# RPS_ARMOR_PCB_2022_V1_0.net
KiCad netlist of a schematic drawn in Altium Designer
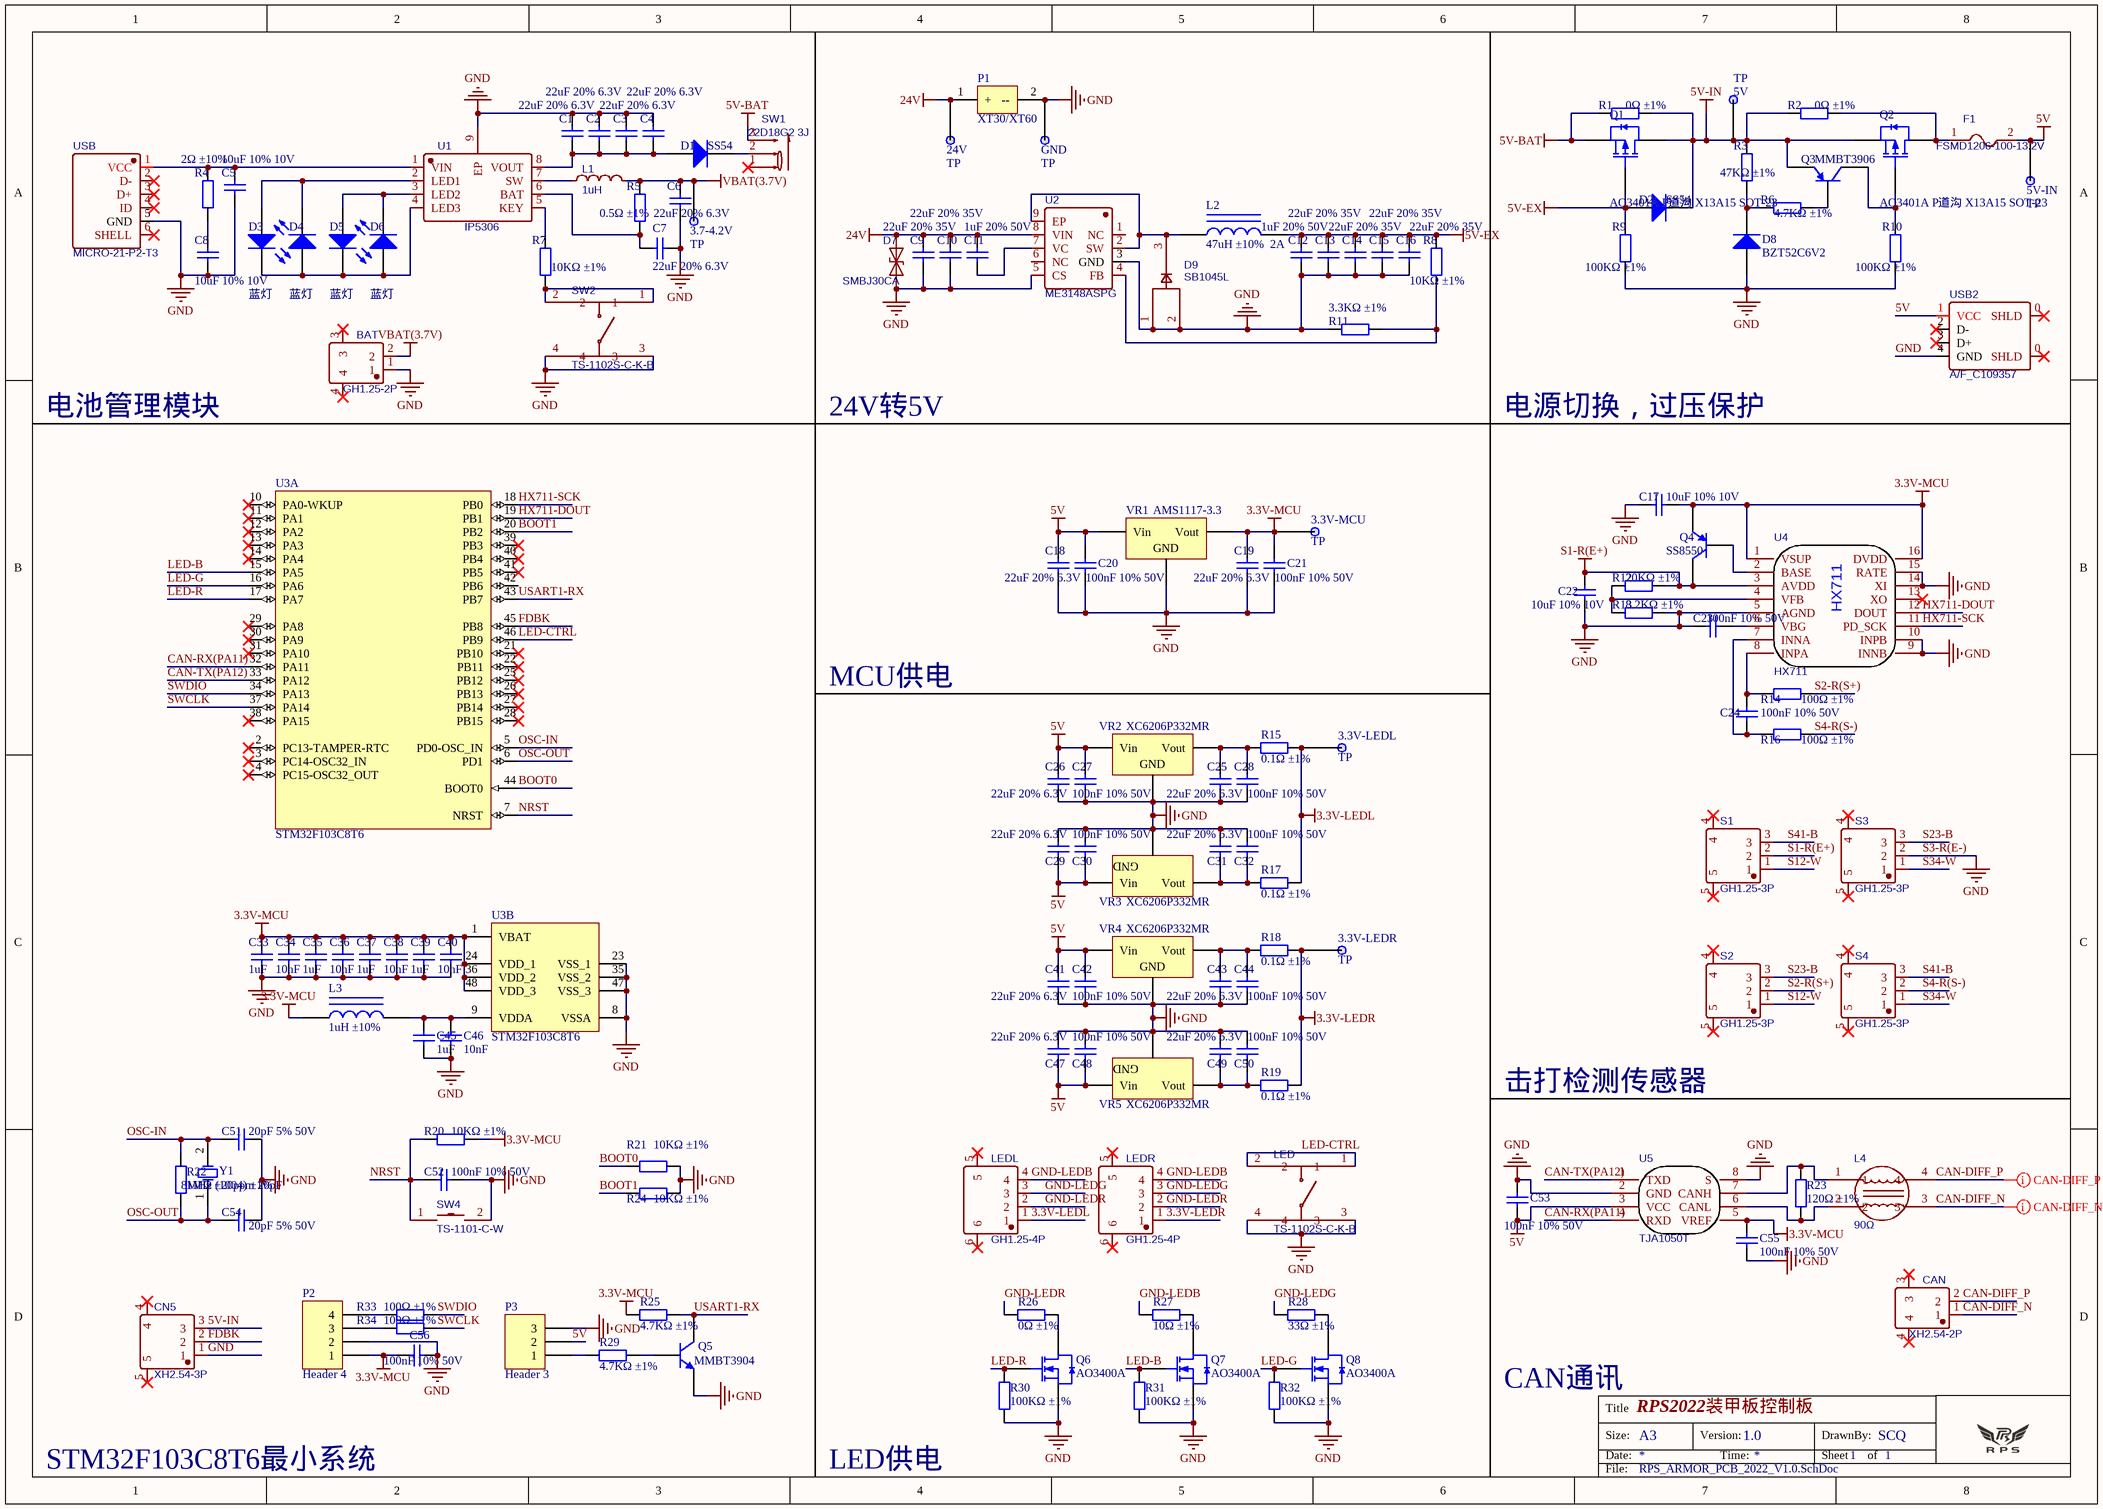
[diagram p0: RPS_ARMOR_PCB_2022_V1.0.SchDoc]

(export (version "E")
  (design (tool "Eeschema 10.0.6"))
  (components
    (comp (ref "3.3V-LEDL")
      (value "TP")
      (footprint "TP")
      (description "测试点")
      (libsource (lib "RPS_ARMOR_PCB_2022_V1.0") (part "TP"))
    )
    (comp (ref "3.3V-LEDR")
      (value "TP")
      (footprint "TP")
      (description "测试点")
      (libsource (lib "RPS_ARMOR_PCB_2022_V1.0") (part "TP"))
    )
    (comp (ref "3.3V-MCU")
      (value "TP")
      (footprint "TP")
      (description "测试点")
      (libsource (lib "RPS_ARMOR_PCB_2022_V1.0") (part "TP"))
    )
    (comp (ref "3.7-4.2V")
      (value "TP")
      (footprint "TP")
      (description "测试点")
      (libsource (lib "RPS_ARMOR_PCB_2022_V1.0") (part "TP"))
    )
    (comp (ref "5V")
      (value "TP")
      (footprint "TP")
      (description "测试点")
      (libsource (lib "RPS_ARMOR_PCB_2022_V1.0") (part "TP"))
    )
    (comp (ref "5V-IN")
      (value "TP")
      (footprint "TP")
      (description "测试点")
      (libsource (lib "RPS_ARMOR_PCB_2022_V1.0") (part "TP"))
    )
    (comp (ref "24V")
      (value "TP")
      (footprint "TP")
      (description "测试点")
      (libsource (lib "RPS_ARMOR_PCB_2022_V1.0") (part "TP"))
    )
    (comp (ref "BAT")
      (value "GH1.25-2P")
      (footprint "GH1.25-WS-2P")
      (description "GH1.25端子")
      (fields
        (field (name "BOM_SUPPLIER PART") "C225125")
        (field (name "BOM_MANUFACTURER PART") "A1257WR-S-2P")
        (field (name "CONTRIBUTOR") "LCSC")
      )
      (libsource (lib "RPS_ARMOR_PCB_2022_V1.0") (part "GH1.25-2P"))
    )
    (comp (ref "C1")
      (value "22uF 20% 6.3V")
      (footprint "0603_C")
      (description "C109448")
      (libsource (lib "Miscellaneous Devices LC") (part "0603 22uF (226) 20% 6.3V"))
    )
    (comp (ref "C2")
      (value "22uF 20% 6.3V")
      (footprint "0603_C")
      (description "C109448")
      (libsource (lib "Miscellaneous Devices LC") (part "0603 22uF (226) 20% 6.3V"))
    )
    (comp (ref "C3")
      (value "22uF 20% 6.3V")
      (footprint "0603_C")
      (description "C109448")
      (libsource (lib "Miscellaneous Devices LC") (part "0603 22uF (226) 20% 6.3V"))
    )
    (comp (ref "C4")
      (value "22uF 20% 6.3V")
      (footprint "0603_C")
      (description "C109448")
      (libsource (lib "Miscellaneous Devices LC") (part "0603 22uF (226) 20% 6.3V"))
    )
    (comp (ref "C5")
      (value "10uF 10% 10V")
      (footprint "0603_C")
      (description "C19702")
      (libsource (lib "Miscellaneous Devices LC") (part "0603 10uF (106) 10% 10V"))
    )
    (comp (ref "C6")
      (value "22uF 20% 6.3V")
      (footprint "0603_C")
      (description "C109448")
      (libsource (lib "Miscellaneous Devices LC") (part "0603 22uF (226) 20% 6.3V"))
    )
    (comp (ref "C7")
      (value "22uF 20% 6.3V")
      (footprint "0603_C")
      (description "C109448")
      (libsource (lib "Miscellaneous Devices LC") (part "0603 22uF (226) 20% 6.3V"))
    )
    (comp (ref "C8")
      (value "10uF 10% 10V")
      (footprint "0603_C")
      (description "C19702")
      (libsource (lib "Miscellaneous Devices LC") (part "0603 10uF (106) 10% 10V"))
    )
    (comp (ref "C9")
      (value "22uF 20% 35V")
      (footprint "1206_C")
      (description "C2835503")
      (libsource (lib "Miscellaneous Devices LC") (part "1206 10uF (106) 10% 50V"))
    )
    (comp (ref "C10")
      (value "22uF 20% 35V")
      (footprint "1206_C")
      (description "C2835503")
      (libsource (lib "Miscellaneous Devices LC") (part "1206 10uF (106) 10% 50V"))
    )
    (comp (ref "C11")
      (value "1uF 20% 50V")
      (footprint "0805_C")
      (description "C2217678")
      (libsource (lib "Miscellaneous Devices LC") (part "0805 1uF (105) 10% 50V"))
    )
    (comp (ref "C12")
      (value "1uF 20% 50V")
      (footprint "0805_C")
      (description "C2217678")
      (libsource (lib "Miscellaneous Devices LC") (part "0805 1uF (105) 10% 50V"))
    )
    (comp (ref "C13")
      (value "22uF 20% 35V")
      (footprint "1206_C")
      (description "C2835503")
      (libsource (lib "Miscellaneous Devices LC") (part "1206 10uF (106) 10% 50V"))
    )
    (comp (ref "C14")
      (value "22uF 20% 35V")
      (footprint "1206_C")
      (description "C2835503")
      (libsource (lib "Miscellaneous Devices LC") (part "1206 10uF (106) 10% 50V"))
    )
    (comp (ref "C15")
      (value "22uF 20% 35V")
      (footprint "1206_C")
      (description "C2835503")
      (libsource (lib "Miscellaneous Devices LC") (part "1206 10uF (106) 10% 50V"))
    )
    (comp (ref "C16")
      (value "22uF 20% 35V")
      (footprint "1206_C")
      (description "C2835503")
      (libsource (lib "Miscellaneous Devices LC") (part "1206 10uF (106) 10% 50V"))
    )
    (comp (ref "C17")
      (value "10uF 10% 10V")
      (footprint "0603_C")
      (description "贴片电容")
      (libsource (lib "Miscellaneous Devices LC") (part "0603 10uF (106) 10% 10V"))
    )
    (comp (ref "C18")
      (value "22uF 20% 6.3V")
      (footprint "0603_C")
      (description "C109448")
      (libsource (lib "Miscellaneous Devices LC") (part "0603 22uF (226) 20% 6.3V"))
    )
    (comp (ref "C19")
      (value "22uF 20% 6.3V")
      (footprint "0603_C")
      (description "C109448")
      (libsource (lib "Miscellaneous Devices LC") (part "0603 22uF (226) 20% 6.3V"))
    )
    (comp (ref "C20")
      (value "100nF 10% 50V")
      (footprint "0603_C")
      (description "贴片电容")
      (libsource (lib "Miscellaneous Devices LC") (part "0603 100nF (104) 10% 50V"))
    )
    (comp (ref "C21")
      (value "100nF 10% 50V")
      (footprint "0603_C")
      (description "贴片电容")
      (libsource (lib "Miscellaneous Devices LC") (part "0603 100nF (104) 10% 50V"))
    )
    (comp (ref "C22")
      (value "10uF 10% 10V")
      (footprint "0603_C")
      (description "贴片电容")
      (libsource (lib "Miscellaneous Devices LC") (part "0603 10uF (106) 10% 10V"))
    )
    (comp (ref "C23")
      (value "100nF 10% 50V")
      (footprint "0603_C")
      (description "贴片电容")
      (libsource (lib "Miscellaneous Devices LC") (part "0603 100nF (104) 10% 50V"))
    )
    (comp (ref "C24")
      (value "100nF 10% 50V")
      (footprint "0603_C")
      (description "贴片电容")
      (libsource (lib "Miscellaneous Devices LC") (part "0603 100nF (104) 10% 50V"))
    )
    (comp (ref "C25")
      (value "22uF 20% 6.3V")
      (footprint "0603_C")
      (description "C109448")
      (libsource (lib "Miscellaneous Devices LC") (part "0603 22uF (226) 20% 6.3V"))
    )
    (comp (ref "C26")
      (value "22uF 20% 6.3V")
      (footprint "0603_C")
      (description "C109448")
      (libsource (lib "Miscellaneous Devices LC") (part "0603 22uF (226) 20% 6.3V"))
    )
    (comp (ref "C27")
      (value "100nF 10% 50V")
      (footprint "0603_C")
      (description "贴片电容")
      (libsource (lib "Miscellaneous Devices LC") (part "0603 100nF (104) 10% 50V"))
    )
    (comp (ref "C28")
      (value "100nF 10% 50V")
      (footprint "0603_C")
      (description "贴片电容")
      (libsource (lib "Miscellaneous Devices LC") (part "0603 100nF (104) 10% 50V"))
    )
    (comp (ref "C29")
      (value "22uF 20% 6.3V")
      (footprint "0603_C")
      (description "C109448")
      (libsource (lib "Miscellaneous Devices LC") (part "0603 22uF (226) 20% 6.3V"))
    )
    (comp (ref "C30")
      (value "100nF 10% 50V")
      (footprint "0603_C")
      (description "贴片电容")
      (libsource (lib "Miscellaneous Devices LC") (part "0603 100nF (104) 10% 50V"))
    )
    (comp (ref "C31")
      (value "22uF 20% 6.3V")
      (footprint "0603_C")
      (description "C109448")
      (libsource (lib "Miscellaneous Devices LC") (part "0603 22uF (226) 20% 6.3V"))
    )
    (comp (ref "C32")
      (value "100nF 10% 50V")
      (footprint "0603_C")
      (description "贴片电容")
      (libsource (lib "Miscellaneous Devices LC") (part "0603 100nF (104) 10% 50V"))
    )
    (comp (ref "C33")
      (value "1uF")
      (footprint "0603_C")
      (description "贴片电容")
      (libsource (lib "Miscellaneous Devices LC") (part "0603 1uF (105) 10% 50V"))
    )
    (comp (ref "C34")
      (value "10nF")
      (footprint "0603_C")
      (description "贴片电容")
      (libsource (lib "Miscellaneous Devices LC") (part "0603 10nF (103) 10% 50V"))
    )
    (comp (ref "C35")
      (value "1uF")
      (footprint "0603_C")
      (description "贴片电容")
      (libsource (lib "Miscellaneous Devices LC") (part "0603 1uF (105) 10% 50V"))
    )
    (comp (ref "C36")
      (value "10nF")
      (footprint "0603_C")
      (description "贴片电容")
      (libsource (lib "Miscellaneous Devices LC") (part "0603 10nF (103) 10% 50V"))
    )
    (comp (ref "C37")
      (value "1uF")
      (footprint "0603_C")
      (description "贴片电容")
      (libsource (lib "Miscellaneous Devices LC") (part "0603 1uF (105) 10% 50V"))
    )
    (comp (ref "C38")
      (value "10nF")
      (footprint "0603_C")
      (description "贴片电容")
      (libsource (lib "Miscellaneous Devices LC") (part "0603 10nF (103) 10% 50V"))
    )
    (comp (ref "C39")
      (value "1uF")
      (footprint "0603_C")
      (description "贴片电容")
      (libsource (lib "Miscellaneous Devices LC") (part "0603 1uF (105) 10% 50V"))
    )
    (comp (ref "C40")
      (value "10nF")
      (footprint "0603_C")
      (description "贴片电容")
      (libsource (lib "Miscellaneous Devices LC") (part "0603 10nF (103) 10% 50V"))
    )
    (comp (ref "C41")
      (value "22uF 20% 6.3V")
      (footprint "0603_C")
      (description "C109448")
      (libsource (lib "Miscellaneous Devices LC") (part "0603 22uF (226) 20% 6.3V"))
    )
    (comp (ref "C42")
      (value "100nF 10% 50V")
      (footprint "0603_C")
      (description "贴片电容")
      (libsource (lib "Miscellaneous Devices LC") (part "0603 100nF (104) 10% 50V"))
    )
    (comp (ref "C43")
      (value "22uF 20% 6.3V")
      (footprint "0603_C")
      (description "C109448")
      (libsource (lib "Miscellaneous Devices LC") (part "0603 22uF (226) 20% 6.3V"))
    )
    (comp (ref "C44")
      (value "100nF 10% 50V")
      (footprint "0603_C")
      (description "贴片电容")
      (libsource (lib "Miscellaneous Devices LC") (part "0603 100nF (104) 10% 50V"))
    )
    (comp (ref "C45")
      (value "1uF")
      (footprint "0603_C")
      (description "贴片电容")
      (libsource (lib "Miscellaneous Devices LC") (part "0603 1uF (105) 10% 50V"))
    )
    (comp (ref "C46")
      (value "10nF")
      (footprint "0603_C")
      (description "贴片电容")
      (libsource (lib "Miscellaneous Devices LC") (part "0603 10nF (103) 10% 50V"))
    )
    (comp (ref "C47")
      (value "22uF 20% 6.3V")
      (footprint "0603_C")
      (description "C109448")
      (libsource (lib "Miscellaneous Devices LC") (part "0603 22uF (226) 20% 6.3V"))
    )
    (comp (ref "C48")
      (value "100nF 10% 50V")
      (footprint "0603_C")
      (description "贴片电容")
      (libsource (lib "Miscellaneous Devices LC") (part "0603 100nF (104) 10% 50V"))
    )
    (comp (ref "C49")
      (value "22uF 20% 6.3V")
      (footprint "0603_C")
      (description "C109448")
      (libsource (lib "Miscellaneous Devices LC") (part "0603 22uF (226) 20% 6.3V"))
    )
    (comp (ref "C50")
      (value "100nF 10% 50V")
      (footprint "0603_C")
      (description "贴片电容")
      (libsource (lib "Miscellaneous Devices LC") (part "0603 100nF (104) 10% 50V"))
    )
    (comp (ref "C51")
      (value "20pF 5% 50V")
      (footprint "0603_C")
      (description "贴片电容")
      (libsource (lib "Miscellaneous Devices LC") (part "0603 20pF (200) 5% 50V"))
    )
    (comp (ref "C52")
      (value "100nF 10% 50V")
      (footprint "0603_C")
      (description "贴片电容")
      (libsource (lib "Miscellaneous Devices LC") (part "0603 100nF (104) 10% 50V"))
    )
    (comp (ref "C53")
      (value "100nF 10% 50V")
      (footprint "0603_C")
      (description "贴片电容")
      (libsource (lib "Miscellaneous Devices LC") (part "0603 100nF (104) 10% 50V"))
    )
    (comp (ref "C54")
      (value "20pF 5% 50V")
      (footprint "0603_C")
      (description "贴片电容")
      (libsource (lib "Miscellaneous Devices LC") (part "0603 20pF (200) 5% 50V"))
    )
    (comp (ref "C55")
      (value "100nF 10% 50V")
      (footprint "0603_C")
      (description "贴片电容")
      (libsource (lib "Miscellaneous Devices LC") (part "0603 100nF (104) 10% 50V"))
    )
    (comp (ref "C56")
      (value "100nF 10% 50V")
      (footprint "0603_C")
      (description "贴片电容")
      (libsource (lib "Miscellaneous Devices LC") (part "0603 100nF (104) 10% 50V"))
    )
    (comp (ref "CAN")
      (value "XH2.54-2P")
      (footprint "XH2.54-LS-2P")
      (description "XH2.54端子")
      (fields
        (field (name "BOM_SUPPLIER PART") "C225125")
        (field (name "BOM_MANUFACTURER PART") "A1257WR-S-2P")
        (field (name "CONTRIBUTOR") "LCSC")
      )
      (libsource (lib "RPS_ARMOR_PCB_2022_V1.0") (part "GH1.25-2P"))
    )
    (comp (ref "CN5")
      (value "XH2.54-3P")
      (footprint "XH2.54-LS-3P")
      (description "XH2.54端子")
      (fields
        (field (name "BOM_SUPPLIER PART") "C225119")
        (field (name "BOM_MANUFACTURER PART") "A1257WV-S-3P")
        (field (name "CONTRIBUTOR") "LCSC")
      )
      (libsource (lib "RPS_ARMOR_PCB_2022_V1.0") (part "GH1.25-3P"))
    )
    (comp (ref "D1")
      (value "SS54")
      (footprint "SMA(DO-214AC)_S1")
      (description "C408258")
      (libsource (lib "Miscellaneous Devices LC") (part "SMA(DO-214AC) SS54"))
    )
    (comp (ref "D2")
      (value "SS54")
      (footprint "SMA(DO-214AC)_S1")
      (description "C408258")
      (libsource (lib "Miscellaneous Devices LC") (part "SMA(DO-214AC) SS54"))
    )
    (comp (ref "D3")
      (value "蓝灯")
      (footprint "0603_LED_S1")
      (description "发光二极管")
      (libsource (lib "Miscellaneous Devices LC") (part "0603 蓝灯"))
    )
    (comp (ref "D4")
      (value "蓝灯")
      (footprint "0603_LED_S1")
      (description "发光二极管")
      (libsource (lib "Miscellaneous Devices LC") (part "0603 蓝灯"))
    )
    (comp (ref "D5")
      (value "蓝灯")
      (footprint "0603_LED_S1")
      (description "发光二极管")
      (libsource (lib "Miscellaneous Devices LC") (part "0603 蓝灯"))
    )
    (comp (ref "D6")
      (value "蓝灯")
      (footprint "0603_LED_S1")
      (description "发光二极管")
      (libsource (lib "Miscellaneous Devices LC") (part "0603 蓝灯"))
    )
    (comp (ref "D7")
      (value "SMBJ30CA")
      (footprint "SMB_L4.6-W3.6-LS5.3-BI")
      (description "C78418")
      (libsource (lib "RPS_ARMOR_PCB_2022_V1.0") (part "SMBJ30CA-C78418"))
    )
    (comp (ref "D8")
      (value "BZT52C6V2")
      (footprint "SOD-123")
      (description "C699157稳压二极管")
      (libsource (lib "Miscellaneous Devices LC") (part "SOD-123 B5819W  SL"))
    )
    (comp (ref "D9")
      (value "SB1045L")
      (footprint "TO-277A_L4.7-W6.1-LS6.6-TR")
      (description "C113945")
      (fields (field (name "CONTRIBUTOR") "LCSC"))
      (libsource (lib "RPS_ARMOR_PCB_2022_V1.0") (part "SB1045L"))
    )
    (comp (ref "F1")
      (value "FSMD1206-100-13.2V")
      (footprint "F1206")
      (description "C883130")
      (fields
        (field (name "BOM_SUPPLIER PART") "C914093")
        (field (name "BOM_MANUFACTURER PART") "BSMD0603L-110")
        (field (name "CONTRIBUTOR") "LCSC")
      )
      (libsource (lib "RPS_ARMOR_PCB_2022_V1.0") (part "FSMD"))
    )
    (comp (ref "GND")
      (value "TP")
      (footprint "TP")
      (description "测试点")
      (libsource (lib "RPS_ARMOR_PCB_2022_V1.0") (part "TP"))
    )
    (comp (ref "L1")
      (value "1uH")
      (footprint "IND-SMD_L7.1-W6.6")
      (description "C87572")
      (fields (field (name "BOM_MANUFACTURER PART") "SPM6530T-1R0M120"))
      (libsource (lib "RPS_ARMOR_PCB_2022_V1.0") (part "1uH"))
    )
    (comp (ref "L2")
      (value "47uH ±10%  2A")
      (footprint "IND-SMD_L7.1-W6.6")
      (description "C149588")
      (libsource (lib "Miscellaneous Devices LC") (part "0805 47uH 10%"))
    )
    (comp (ref "L3")
      (value "1uH ±10%")
      (footprint "0805_L")
      (description "C1042")
      (libsource (lib "Miscellaneous Devices LC") (part "0805 1uH 10%"))
    )
    (comp (ref "L4")
      (value "90Ω")
      (footprint "FILTER-SMD_4P-L2.0-W1.2-BL")
      (description "C307642")
      (fields
        (field (name "BOM_MANUFACTURER PART") "ACM2012H-900-2P-T00")
        (field (name "BOM_SUPPLIER PART") "C76575")
      )
      (libsource (lib "RPS_ARMOR_PCB_2022_V1.0") (part "90Ω @100MHz"))
    )
    (comp (ref "LED")
      (value "TS-1102S-C-K-B")
      (footprint "TSW SMD-6*6*8")
      (description "C136667")
      (fields (field (name "BOM_SUPPLIER PART") "C381049") (field (name "CONTRIBUTOR") "LCSC"))
      (libsource (lib "RPS_ARMOR_PCB_2022_V1.0") (part "TS-1102S-C-K-B"))
    )
    (comp (ref "LEDL")
      (value "GH1.25-4P")
      (footprint "GH1.25-WS-4P")
      (description "GH1.25端子")
      (fields
        (field (name "BOM_SUPPLIER PART") "C225120")
        (field (name "BOM_MANUFACTURER PART") "A1257WV-S-4P")
        (field (name "CONTRIBUTOR") "LCSC")
      )
      (libsource (lib "RPS_ARMOR_PCB_2022_V1.0") (part "GH1.25-4P"))
    )
    (comp (ref "LEDR")
      (value "GH1.25-4P")
      (footprint "GH1.25-WS-4P")
      (description "GH1.25端子")
      (fields
        (field (name "BOM_SUPPLIER PART") "C225120")
        (field (name "BOM_MANUFACTURER PART") "A1257WV-S-4P")
        (field (name "CONTRIBUTOR") "LCSC")
      )
      (libsource (lib "RPS_ARMOR_PCB_2022_V1.0") (part "GH1.25-4P"))
    )
    (comp (ref "P1")
      (value "XT30/XT60")
      (footprint "XT30UPB-M")
      (description "XT端子")
      (libsource (lib "RPS_ARMOR_PCB_2022_V1.0") (part "XT30/XT60"))
    )
    (comp (ref "P2")
      (value "Header 4")
      (footprint "HDR2.54-LI-4P")
      (description "Header, 4-Pin")
      (fields (field (name "PUBLISHER") "Altium Limited"))
      (libsource (lib "Miscellaneous Connectors") (part "Header 4"))
    )
    (comp (ref "P3")
      (value "Header 3")
      (footprint "HDR2.54-LI-3P")
      (description "Header, 3-Pin")
      (fields (field (name "PUBLISHER") "Altium Limited"))
      (libsource (lib "Miscellaneous Connectors") (part "Header 3"))
    )
    (comp (ref "Q1")
      (value "AO3401A P道沟 X13A15 SOT-23")
      (footprint "SOT-23-3L")
      (description "MOS(场效应管)")
      (libsource (lib "Miscellaneous Devices LC") (part "AO3401A P道沟 X13A15 SOT-23"))
    )
    (comp (ref "Q2")
      (value "AO3401A P道沟 X13A15 SOT-23")
      (footprint "SOT-23-3L")
      (description "MOS(场效应管)")
      (libsource (lib "Miscellaneous Devices LC") (part "AO3401A P道沟 X13A15 SOT-23"))
    )
    (comp (ref "Q3")
      (value "MMBT3906")
      (footprint "SOT-23(SOT-23-3)")
      (description "C53444 三极管")
      (libsource (lib "Miscellaneous Devices LC") (part "SOT-23 MMBT5401 2L"))
    )
    (comp (ref "Q4")
      (value "SS8550")
      (footprint "SOT-23(SOT-23-3)")
      (description "C8542")
      (libsource (lib "Miscellaneous Devices LC") (part "SOT-23 SS8550 Y2"))
    )
    (comp (ref "Q5")
      (value "MMBT3904")
      (footprint "SOT-23(SOT-23-3)")
      (description "C20526三极管")
      (libsource (lib "Miscellaneous Devices LC") (part "SOT-23 MMBT5551  G1"))
    )
    (comp (ref "Q6")
      (value "AO3400A")
      (footprint "SOT-23-3L")
      (description "MOS(场效应管)")
      (libsource (lib "Miscellaneous Devices LC") (part "AO3400A N道沟 X0YV1T SOT-23"))
    )
    (comp (ref "Q7")
      (value "AO3400A")
      (footprint "SOT-23-3L")
      (description "MOS(场效应管)")
      (libsource (lib "Miscellaneous Devices LC") (part "AO3400A N道沟 X0YV1T SOT-23"))
    )
    (comp (ref "Q8")
      (value "AO3400A")
      (footprint "SOT-23-3L")
      (description "MOS(场效应管)")
      (libsource (lib "Miscellaneous Devices LC") (part "AO3400A N道沟 X0YV1T SOT-23"))
    )
    (comp (ref "R1")
      (value "0Ω ±1%")
      (footprint "0402_R")
      (description "贴片电阻")
      (libsource (lib "Miscellaneous Devices LC") (part "0402 0Ω (0R0) 1%"))
    )
    (comp (ref "R2")
      (value "0Ω ±1%")
      (footprint "0402_R")
      (description "贴片电阻")
      (libsource (lib "Miscellaneous Devices LC") (part "0402 0Ω (0R0) 1%"))
    )
    (comp (ref "R3")
      (value "47KΩ ±1%")
      (footprint "0603_R")
      (description "贴片电阻")
      (libsource (lib "Miscellaneous Devices LC") (part "0603 47KΩ (4702) 1%"))
    )
    (comp (ref "R4")
      (value "2Ω ±10%")
      (footprint "0603_R")
      (description "C25225")
      (libsource (lib "Miscellaneous Devices LC") (part "0603 1Ω (1R00) 1%"))
    )
    (comp (ref "R5")
      (value "0.5Ω ±1%")
      (footprint "1206_R")
      (description "C104947")
      (libsource (lib "") (part "1206 0.1Ω (R100) 1%_1"))
    )
    (comp (ref "R6")
      (value "4.7KΩ ±1%")
      (footprint "0603_R")
      (description "贴片电阻")
      (libsource (lib "Miscellaneous Devices LC") (part "0603 4.7KΩ (4701) 1%"))
    )
    (comp (ref "R7")
      (value "10KΩ ±1%")
      (footprint "0603_R")
      (description "贴片电阻")
      (libsource (lib "") (part "0603 10KΩ (1002) 1%_1"))
    )
    (comp (ref "R8")
      (value "10KΩ ±1%")
      (footprint "0603_R")
      (description "贴片电阻")
      (libsource (lib "") (part "0603 10KΩ (1002) 1%_1"))
    )
    (comp (ref "R9")
      (value "100KΩ ±1%")
      (footprint "0603_R")
      (description "贴片电阻")
      (libsource (lib "Miscellaneous Devices LC") (part "0603 100KΩ (1003) 1%"))
    )
    (comp (ref "R10")
      (value "100KΩ ±1%")
      (footprint "0603_R")
      (description "贴片电阻")
      (libsource (lib "Miscellaneous Devices LC") (part "0603 100KΩ (1003) 1%"))
    )
    (comp (ref "R11")
      (value "3.3KΩ ±1%")
      (footprint "0603_R")
      (description "贴片电阻")
      (libsource (lib "Miscellaneous Devices LC") (part "0603 3.3KΩ (3301) 1%"))
    )
    (comp (ref "R12")
      (value "20KΩ ±1%")
      (footprint "0603_R")
      (description "C4184")
      (libsource (lib "Miscellaneous Devices LC") (part "0603 20KΩ (2002) 1%"))
    )
    (comp (ref "R13")
      (value "8.2KΩ ±1%")
      (footprint "0603_R")
      (description "C25981")
      (libsource (lib "Miscellaneous Devices LC") (part "0603 8.2KΩ (8201) 1%"))
    )
    (comp (ref "R14")
      (value "100Ω ±1%")
      (footprint "0603_R")
      (description "贴片电阻")
      (libsource (lib "Miscellaneous Devices LC") (part "0603 100Ω (1000) 1%"))
    )
    (comp (ref "R15")
      (value "0.1Ω ±1%")
      (footprint "1206_R")
      (description "贴片电阻")
      (libsource (lib "Miscellaneous Devices LC") (part "1206 0.1Ω (R100) 1%"))
    )
    (comp (ref "R16")
      (value "100Ω ±1%")
      (footprint "0603_R")
      (description "贴片电阻")
      (libsource (lib "Miscellaneous Devices LC") (part "0603 100Ω (1000) 1%"))
    )
    (comp (ref "R17")
      (value "0.1Ω ±1%")
      (footprint "1206_R")
      (description "贴片电阻")
      (libsource (lib "Miscellaneous Devices LC") (part "1206 0.1Ω (R100) 1%"))
    )
    (comp (ref "R18")
      (value "0.1Ω ±1%")
      (footprint "1206_R")
      (description "贴片电阻")
      (libsource (lib "Miscellaneous Devices LC") (part "1206 0.1Ω (R100) 1%"))
    )
    (comp (ref "R19")
      (value "0.1Ω ±1%")
      (footprint "1206_R")
      (description "贴片电阻")
      (libsource (lib "Miscellaneous Devices LC") (part "1206 0.1Ω (R100) 1%"))
    )
    (comp (ref "R20")
      (value "10KΩ ±1%")
      (footprint "0603_R")
      (description "贴片电阻")
      (libsource (lib "Miscellaneous Devices LC") (part "0603 10KΩ (1002) 1%"))
    )
    (comp (ref "R21")
      (value "10KΩ ±1%")
      (footprint "0603_R")
      (description "贴片电阻")
      (libsource (lib "Miscellaneous Devices LC") (part "0603 10KΩ (1002) 1%"))
    )
    (comp (ref "R22")
      (value "1MΩ (1004) ±1%")
      (footprint "0603_R")
      (description "贴片电阻")
      (libsource (lib "Miscellaneous Devices LC") (part "0603 1MΩ (1004) 1%"))
    )
    (comp (ref "R23")
      (value "120Ω ±1%")
      (footprint "0603_R")
      (description "贴片电阻")
      (libsource (lib "Miscellaneous Devices LC") (part "0603 120Ω (1200) 1%"))
    )
    (comp (ref "R24")
      (value "10KΩ ±1%")
      (footprint "0603_R")
      (description "贴片电阻")
      (libsource (lib "Miscellaneous Devices LC") (part "0603 10KΩ (1002) 1%"))
    )
    (comp (ref "R25")
      (value "4.7KΩ ±1%")
      (footprint "0603_R")
      (description "贴片电阻")
      (libsource (lib "Miscellaneous Devices LC") (part "0603 4.7KΩ (4701) 1%"))
    )
    (comp (ref "R26")
      (value "0Ω ±1%")
      (footprint "0603_R")
      (description "贴片电阻")
      (libsource (lib "Miscellaneous Devices LC") (part "0603 1KΩ (1001) 1%"))
    )
    (comp (ref "R27")
      (value "10Ω ±1%")
      (footprint "0603_R")
      (description "贴片电阻")
      (libsource (lib "Miscellaneous Devices LC") (part "0603 1KΩ (1001) 1%"))
    )
    (comp (ref "R28")
      (value "33Ω ±1%")
      (footprint "0603_R")
      (description "贴片电阻")
      (libsource (lib "Miscellaneous Devices LC") (part "0603 1KΩ (1001) 1%"))
    )
    (comp (ref "R29")
      (value "4.7KΩ ±1%")
      (footprint "0603_R")
      (description "贴片电阻")
      (libsource (lib "Miscellaneous Devices LC") (part "0603 4.7KΩ (4701) 1%"))
    )
    (comp (ref "R30")
      (value "100KΩ ±1%")
      (footprint "0603_R")
      (description "贴片电阻")
      (libsource (lib "Miscellaneous Devices LC") (part "0603 100KΩ (1003) 1%"))
    )
    (comp (ref "R31")
      (value "100KΩ ±1%")
      (footprint "0603_R")
      (description "贴片电阻")
      (libsource (lib "Miscellaneous Devices LC") (part "0603 100KΩ (1003) 1%"))
    )
    (comp (ref "R32")
      (value "100KΩ ±1%")
      (footprint "0603_R")
      (description "贴片电阻")
      (libsource (lib "Miscellaneous Devices LC") (part "0603 100KΩ (1003) 1%"))
    )
    (comp (ref "R33")
      (value "100Ω ±1%")
      (footprint "0603_R")
      (description "贴片电阻")
      (libsource (lib "Miscellaneous Devices LC") (part "0603 100Ω (1000) 1%"))
    )
    (comp (ref "R34")
      (value "100Ω ±1%")
      (footprint "0603_R")
      (description "贴片电阻")
      (libsource (lib "Miscellaneous Devices LC") (part "0603 100Ω (1000) 1%"))
    )
    (comp (ref "S1")
      (value "GH1.25-3P")
      (footprint "GH1.25-WS-3P")
      (description "GH1.25端子")
      (fields
        (field (name "BOM_SUPPLIER PART") "C225119")
        (field (name "BOM_MANUFACTURER PART") "A1257WV-S-3P")
        (field (name "CONTRIBUTOR") "LCSC")
      )
      (libsource (lib "RPS_ARMOR_PCB_2022_V1.0") (part "GH1.25-3P"))
    )
    (comp (ref "S2")
      (value "GH1.25-3P")
      (footprint "GH1.25-WS-3P")
      (description "GH1.25端子")
      (fields
        (field (name "BOM_SUPPLIER PART") "C225119")
        (field (name "BOM_MANUFACTURER PART") "A1257WV-S-3P")
        (field (name "CONTRIBUTOR") "LCSC")
      )
      (libsource (lib "RPS_ARMOR_PCB_2022_V1.0") (part "GH1.25-3P"))
    )
    (comp (ref "S3")
      (value "GH1.25-3P")
      (footprint "GH1.25-WS-3P")
      (description "GH1.25端子")
      (fields
        (field (name "BOM_SUPPLIER PART") "C225119")
        (field (name "BOM_MANUFACTURER PART") "A1257WV-S-3P")
        (field (name "CONTRIBUTOR") "LCSC")
      )
      (libsource (lib "RPS_ARMOR_PCB_2022_V1.0") (part "GH1.25-3P"))
    )
    (comp (ref "S4")
      (value "GH1.25-3P")
      (footprint "GH1.25-WS-3P")
      (description "GH1.25端子")
      (fields
        (field (name "BOM_SUPPLIER PART") "C225119")
        (field (name "BOM_MANUFACTURER PART") "A1257WV-S-3P")
        (field (name "CONTRIBUTOR") "LCSC")
      )
      (libsource (lib "RPS_ARMOR_PCB_2022_V1.0") (part "GH1.25-3P"))
    )
    (comp (ref "SW1")
      (value "22D18G2 3J")
      (footprint "SW-SMD_MST-22D18G23J")
      (description "C514026")
      (fields
        (field (name "BOM_SUPPLIER PART") "C668586")
        (field (name "BOM_MANUFACTURER PART") "MST-22D18G2 3J")
        (field (name "CONTRIBUTOR") "LCSC")
      )
      (libsource (lib "器件库") (part "MST-22D18G2 3J"))
    )
    (comp (ref "SW2")
      (value "TS-1102S-C-K-B")
      (footprint "TSW SMD-6*6*8")
      (description "C136667")
      (fields (field (name "BOM_SUPPLIER PART") "C381049") (field (name "CONTRIBUTOR") "LCSC"))
      (libsource (lib "RPS_ARMOR_PCB_2022_V1.0") (part "TS-1102S-C-K-B"))
    )
    (comp (ref "SW4")
      (value "TS-1101-C-W")
      (footprint "SW-SMD_L6.0-W3.3-LS8.0")
      (description "C318938")
      (fields (field (name "CONTRIBUTOR") "LCSC"))
      (libsource (lib "RPS_ARMOR_PCB_2022_V1.0") (part "TS-1101-C-W"))
    )
    (comp (ref "U1")
      (value "IP5306")
      (footprint "ESOP-8_L4.9-W3.9-P1.27-LS6.0-BL-EP")
      (description "C181692")
      (fields (field (name "CONTRIBUTOR") "LCSC"))
      (libsource (lib "RPS_ARMOR_PCB_2022_V1.0") (part "IP5306"))
    )
    (comp (ref "U2")
      (value "ME3148ASPG")
      (footprint "ESOP-8_L4.9-W3.9-P1.27-LS6.0-BL-EP")
      (description "C2683415")
      (fields (field (name "CONTRIBUTOR") "LCSC"))
      (libsource (lib "RPS_ARMOR_PCB_2022_V1.0") (part "ME3148ASPG"))
    )
    (comp (ref "U3")
      (value "STM32F103C8T6")
      (footprint "LQFP-48_7x7x05P")
      (description "ARM")
      (libsource (lib "Miscellaneous Devices LC") (part "STM32F103C8T6"))
    )
    (comp (ref "U4")
      (value "HX711")
      (footprint "SOP16")
      (fields (field (name "BOM_SUPPLIER PART") "C43656"))
      (libsource (lib "RPS_ARMOR_PCB_2022_V1.0") (part "HX711"))
    )
    (comp (ref "U5")
      (value "TJA1050T")
      (footprint "SOIC-8_L5.0-W4.0-P1.27-LS6.0-BL")
      (description "C6952(C313021)")
      (fields
        (field (name "BOM_MANUFACTURER PART") "TJA1050T/CM,118")
        (field (name "BOM_SUPPLIER PART") "C6952")
      )
      (libsource (lib "RPS_ARMOR_PCB_2022_V1.0") (part "TJA1050T"))
    )
    (comp (ref "USB")
      (value "MICRO-21-P2-T3")
      (footprint "MICRO-USB-SMD_LI")
      (description "C2834965 Micro-B 母座 立贴")
      (fields (field (name "BOM_SUPPLIER PART") "C2834965") (field (name "CONTRIBUTOR") "LCSC"))
      (libsource (lib "RPS_ARMOR_PCB_2022_V1.0") (part "MICRO-USB-SMD_LI"))
    )
    (comp (ref "USB2")
      (value "A/F_C109357")
      (footprint "USB-A-TH_USB-A-F-1")
      (fields (field (name "BOM_SUPPLIER PART") "C109357") (field (name "CONTRIBUTOR") "立创EDA官方封装库"))
      (libsource (lib "RPS_ARMOR_PCB_2022_V1.0") (part "A/F_C109357"))
    )
    (comp (ref "VR1")
      (value "AMS1117-3.3")
      (footprint "SOT-223")
      (description "低压差线性稳压(LDO)")
      (libsource (lib "Miscellaneous Devices LC") (part "SOT-223 AMS1117-3.3"))
    )
    (comp (ref "VR2")
      (value "XC6206P332MR")
      (footprint "SOT-23-3L")
      (description "低压差线性稳压(LDO)")
      (libsource (lib "Miscellaneous Devices LC") (part "SOT-23 XC6206P332MR"))
    )
    (comp (ref "VR3")
      (value "XC6206P332MR")
      (footprint "SOT-23-3L")
      (description "低压差线性稳压(LDO)")
      (libsource (lib "") (part "SOT-23 XC6206P332MR_1"))
    )
    (comp (ref "VR4")
      (value "XC6206P332MR")
      (footprint "SOT-23-3L")
      (description "低压差线性稳压(LDO)")
      (libsource (lib "Miscellaneous Devices LC") (part "SOT-23 XC6206P332MR"))
    )
    (comp (ref "VR5")
      (value "XC6206P332MR")
      (footprint "SOT-23-3L")
      (description "低压差线性稳压(LDO)")
      (libsource (lib "") (part "SOT-23 XC6206P332MR_1"))
    )
    (comp (ref "Y1")
      (value "8MHz ±20ppm 20pF")
      (footprint "SMD-5032_2P")
      (description "贴片晶振")
      (libsource (lib "Miscellaneous Devices LC") (part "SMD-5032_2P 8MHz 20ppm 20pF"))
    )
  )
  (nets
    (net (code "1") (name "/BOOT0") (class "Default")
      (node (ref "R21") (pin "1") (pinfunction "1_1") (pintype "passive"))
      (node (ref "U3") (pin "44") (pinfunction "BOOT0_44") (pintype "input"))
    )
    (net (code "2") (name "/BOOT1") (class "Default")
      (node (ref "R24") (pin "1") (pinfunction "1_1") (pintype "passive"))
      (node (ref "U3") (pin "20") (pinfunction "PB2_20") (pintype "bidirectional"))
    )
    (net (code "3") (name "/CAN-DIFF_N") (class "Default")
      (node (ref "CAN") (pin "1") (pinfunction "1_1") (pintype "passive"))
      (node (ref "L4") (pin "3") (pinfunction "3_3") (pintype "passive"))
    )
    (net (code "4") (name "/CAN-DIFF_P") (class "Default")
      (node (ref "CAN") (pin "2") (pinfunction "2_2") (pintype "passive"))
      (node (ref "L4") (pin "4") (pinfunction "4_4") (pintype "passive"))
    )
    (net (code "5") (name "/CAN-RX(PA11)") (class "Default")
      (node (ref "U3") (pin "32") (pinfunction "PA11_32") (pintype "bidirectional"))
      (node (ref "U5") (pin "4") (pinfunction "RXD_4") (pintype "passive"))
    )
    (net (code "6") (name "/CAN-TX(PA12)") (class "Default")
      (node (ref "U3") (pin "33") (pinfunction "PA12_33") (pintype "bidirectional"))
      (node (ref "U5") (pin "1") (pinfunction "TXD_1") (pintype "passive"))
    )
    (net (code "7") (name "/FDBK") (class "Default")
      (node (ref "CN5") (pin "2") (pinfunction "2_2") (pintype "passive"))
      (node (ref "U3") (pin "45") (pinfunction "PB8_45") (pintype "bidirectional"))
    )
    (net (code "8") (name "/GND-LEDB") (class "Default")
      (node (ref "LEDL") (pin "4") (pinfunction "4_4") (pintype "passive"))
      (node (ref "LEDR") (pin "4") (pinfunction "4_4") (pintype "passive"))
      (node (ref "R27") (pin "2") (pinfunction "2_2") (pintype "passive"))
    )
    (net (code "9") (name "/GND-LEDG") (class "Default")
      (node (ref "LEDL") (pin "3") (pinfunction "3_3") (pintype "passive"))
      (node (ref "LEDR") (pin "3") (pinfunction "3_3") (pintype "passive"))
      (node (ref "R28") (pin "2") (pinfunction "2_2") (pintype "passive"))
    )
    (net (code "10") (name "/GND-LEDR") (class "Default")
      (node (ref "LEDL") (pin "2") (pinfunction "2_2") (pintype "passive"))
      (node (ref "LEDR") (pin "2") (pinfunction "2_2") (pintype "passive"))
      (node (ref "R26") (pin "2") (pinfunction "2_2") (pintype "passive"))
    )
    (net (code "11") (name "/HX711-DOUT") (class "Default")
      (node (ref "U3") (pin "19") (pinfunction "PB1_19") (pintype "bidirectional"))
      (node (ref "U4") (pin "12") (pinfunction "DOUT_12") (pintype "passive"))
    )
    (net (code "12") (name "/HX711-SCK") (class "Default")
      (node (ref "U3") (pin "18") (pinfunction "PB0_18") (pintype "bidirectional"))
      (node (ref "U4") (pin "11") (pinfunction "PD_SCK_11") (pintype "passive"))
    )
    (net (code "13") (name "/LED-B") (class "Default")
      (node (ref "Q7") (pin "1") (pinfunction "G_1") (pintype "passive"))
      (node (ref "R31") (pin "2") (pinfunction "2_2") (pintype "passive"))
      (node (ref "U3") (pin "15") (pinfunction "PA5_15") (pintype "bidirectional"))
    )
    (net (code "14") (name "/LED-CTRL") (class "Default")
      (node (ref "LED") (pin "1") (pinfunction "1_1") (pintype "passive"))
      (node (ref "LED") (pin "2") (pinfunction "2_2") (pintype "passive"))
      (node (ref "U3") (pin "46") (pinfunction "PB9_46") (pintype "bidirectional"))
    )
    (net (code "15") (name "/LED-G") (class "Default")
      (node (ref "Q8") (pin "1") (pinfunction "G_1") (pintype "passive"))
      (node (ref "R32") (pin "2") (pinfunction "2_2") (pintype "passive"))
      (node (ref "U3") (pin "16") (pinfunction "PA6_16") (pintype "bidirectional"))
    )
    (net (code "16") (name "/LED-R") (class "Default")
      (node (ref "Q6") (pin "1") (pinfunction "G_1") (pintype "passive"))
      (node (ref "R30") (pin "2") (pinfunction "2_2") (pintype "passive"))
      (node (ref "U3") (pin "17") (pinfunction "PA7_17") (pintype "bidirectional"))
    )
    (net (code "17") (name "/NRST") (class "Default")
      (node (ref "C52") (pin "1") (pinfunction "1_1") (pintype "passive"))
      (node (ref "R20") (pin "1") (pinfunction "1_1") (pintype "passive"))
      (node (ref "SW4") (pin "1") (pinfunction "1_1") (pintype "passive"))
      (node (ref "U3") (pin "7") (pinfunction "NRST_7") (pintype "bidirectional"))
    )
    (net (code "18") (name "/OSC-IN") (class "Default")
      (node (ref "C51") (pin "1") (pinfunction "1_1") (pintype "passive"))
      (node (ref "R22") (pin "2") (pinfunction "2_2") (pintype "passive"))
      (node (ref "U3") (pin "5") (pinfunction "PD0-OSC_IN_5") (pintype "bidirectional"))
      (node (ref "Y1") (pin "2") (pinfunction "OSC2_2") (pintype "passive"))
    )
    (net (code "19") (name "/OSC-OUT") (class "Default")
      (node (ref "C54") (pin "1") (pinfunction "1_1") (pintype "passive"))
      (node (ref "R22") (pin "1") (pinfunction "1_1") (pintype "passive"))
      (node (ref "U3") (pin "6") (pinfunction "PD1_6") (pintype "bidirectional"))
      (node (ref "Y1") (pin "1") (pinfunction "OSC1_1") (pintype "passive"))
    )
    (net (code "20") (name "/S2-R(S+)") (class "Default")
      (node (ref "R14") (pin "2") (pinfunction "2_2") (pintype "passive"))
      (node (ref "S2") (pin "2") (pinfunction "2_2") (pintype "passive"))
    )
    (net (code "21") (name "/S4-R(S-)") (class "Default")
      (node (ref "R16") (pin "2") (pinfunction "2_2") (pintype "passive"))
      (node (ref "S4") (pin "2") (pinfunction "2_2") (pintype "passive"))
    )
    (net (code "22") (name "/S12-W") (class "Default")
      (node (ref "S1") (pin "1") (pinfunction "1_1") (pintype "passive"))
      (node (ref "S2") (pin "1") (pinfunction "1_1") (pintype "passive"))
    )
    (net (code "23") (name "/S23-B") (class "Default")
      (node (ref "S2") (pin "3") (pinfunction "3_3") (pintype "passive"))
      (node (ref "S3") (pin "3") (pinfunction "3_3") (pintype "passive"))
    )
    (net (code "24") (name "/S34-W") (class "Default")
      (node (ref "S3") (pin "1") (pinfunction "1_1") (pintype "passive"))
      (node (ref "S4") (pin "1") (pinfunction "1_1") (pintype "passive"))
    )
    (net (code "25") (name "/S41-B") (class "Default")
      (node (ref "S1") (pin "3") (pinfunction "3_3") (pintype "passive"))
      (node (ref "S4") (pin "3") (pinfunction "3_3") (pintype "passive"))
    )
    (net (code "26") (name "/SWCLK") (class "Default")
      (node (ref "R34") (pin "2") (pinfunction "2_2") (pintype "passive"))
      (node (ref "U3") (pin "37") (pinfunction "PA14_37") (pintype "bidirectional"))
    )
    (net (code "27") (name "/SWDIO") (class "Default")
      (node (ref "R33") (pin "2") (pinfunction "2_2") (pintype "passive"))
      (node (ref "U3") (pin "34") (pinfunction "PA13_34") (pintype "bidirectional"))
    )
    (net (code "28") (name "/USART1-RX") (class "Default")
      (node (ref "Q5") (pin "3") (pinfunction "C_3") (pintype "passive"))
      (node (ref "R25") (pin "2") (pinfunction "2_2") (pintype "passive"))
      (node (ref "U3") (pin "43") (pinfunction "PB7_43") (pintype "bidirectional"))
    )
    (net (code "29") (name "3.3V-LEDL") (class "Default")
      (node (ref "3.3V-LEDL") (pin "1") (pinfunction "1_1") (pintype "passive"))
      (node (ref "LEDL") (pin "1") (pinfunction "1_1") (pintype "passive"))
      (node (ref "R15") (pin "2") (pinfunction "2_2") (pintype "passive"))
      (node (ref "R17") (pin "2") (pinfunction "2_2") (pintype "passive"))
    )
    (net (code "30") (name "3.3V-LEDR") (class "Default")
      (node (ref "3.3V-LEDR") (pin "1") (pinfunction "1_1") (pintype "passive"))
      (node (ref "LEDR") (pin "1") (pinfunction "1_1") (pintype "passive"))
      (node (ref "R18") (pin "2") (pinfunction "2_2") (pintype "passive"))
      (node (ref "R19") (pin "2") (pinfunction "2_2") (pintype "passive"))
    )
    (net (code "31") (name "3.3V-MCU") (class "Default")
      (node (ref "3.3V-MCU") (pin "1") (pinfunction "1_1") (pintype "passive"))
      (node (ref "C17") (pin "2") (pinfunction "2_2") (pintype "passive"))
      (node (ref "C19") (pin "2") (pinfunction "2_2") (pintype "passive"))
      (node (ref "C21") (pin "2") (pinfunction "2_2") (pintype "passive"))
      (node (ref "C33") (pin "2") (pinfunction "2_2") (pintype "passive"))
      (node (ref "C34") (pin "2") (pinfunction "2_2") (pintype "passive"))
      (node (ref "C35") (pin "2") (pinfunction "2_2") (pintype "passive"))
      (node (ref "C36") (pin "2") (pinfunction "2_2") (pintype "passive"))
      (node (ref "C37") (pin "2") (pinfunction "2_2") (pintype "passive"))
      (node (ref "C38") (pin "2") (pinfunction "2_2") (pintype "passive"))
      (node (ref "C39") (pin "2") (pinfunction "2_2") (pintype "passive"))
      (node (ref "C40") (pin "2") (pinfunction "2_2") (pintype "passive"))
      (node (ref "C55") (pin "2") (pinfunction "2_2") (pintype "passive"))
      (node (ref "C56") (pin "1") (pinfunction "1_1") (pintype "passive"))
      (node (ref "L3") (pin "1") (pinfunction "1_1") (pintype "passive"))
      (node (ref "P2") (pin "1") (pinfunction "1_1") (pintype "passive"))
      (node (ref "Q4") (pin "2") (pinfunction "E_2") (pintype "passive"))
      (node (ref "R20") (pin "2") (pinfunction "2_2") (pintype "passive"))
      (node (ref "R25") (pin "1") (pinfunction "1_1") (pintype "passive"))
      (node (ref "U3") (pin "1") (pinfunction "VBAT_1") (pintype "power_in"))
      (node (ref "U3") (pin "24") (pinfunction "VDD_1_24") (pintype "power_in"))
      (node (ref "U3") (pin "36") (pinfunction "VDD_2_36") (pintype "power_in"))
      (node (ref "U3") (pin "48") (pinfunction "VDD_3_48") (pintype "power_in"))
      (node (ref "U4") (pin "1") (pinfunction "VSUP_1") (pintype "passive"))
      (node (ref "U4") (pin "16") (pinfunction "DVDD_16") (pintype "passive"))
      (node (ref "U5") (pin "5") (pinfunction "VREF_5") (pintype "passive"))
      (node (ref "VR1") (pin "2") (pinfunction "Vout_2") (pintype "passive"))
    )
    (net (code "32") (name "5V") (class "Default")
      (node (ref "5V-IN") (pin "1") (pinfunction "1_1") (pintype "passive"))
      (node (ref "C18") (pin "2") (pinfunction "2_2") (pintype "passive"))
      (node (ref "C20") (pin "2") (pinfunction "2_2") (pintype "passive"))
      (node (ref "C26") (pin "2") (pinfunction "2_2") (pintype "passive"))
      (node (ref "C27") (pin "2") (pinfunction "2_2") (pintype "passive"))
      (node (ref "C29") (pin "2") (pinfunction "2_2") (pintype "passive"))
      (node (ref "C30") (pin "2") (pinfunction "2_2") (pintype "passive"))
      (node (ref "C41") (pin "2") (pinfunction "2_2") (pintype "passive"))
      (node (ref "C42") (pin "2") (pinfunction "2_2") (pintype "passive"))
      (node (ref "C47") (pin "2") (pinfunction "2_2") (pintype "passive"))
      (node (ref "C48") (pin "2") (pinfunction "2_2") (pintype "passive"))
      (node (ref "C53") (pin "1") (pinfunction "1_1") (pintype "passive"))
      (node (ref "F1") (pin "2") (pinfunction "2_2") (pintype "passive"))
      (node (ref "P3") (pin "2") (pinfunction "2_2") (pintype "passive"))
      (node (ref "U5") (pin "3") (pinfunction "VCC_3") (pintype "passive"))
      (node (ref "USB2") (pin "1") (pinfunction "VCC_1") (pintype "passive"))
      (node (ref "VR1") (pin "3") (pinfunction "Vin_3") (pintype "passive"))
      (node (ref "VR2") (pin "3") (pinfunction "Vin_3") (pintype "passive"))
      (node (ref "VR3") (pin "3") (pinfunction "Vin_3") (pintype "passive"))
      (node (ref "VR4") (pin "3") (pinfunction "Vin_3") (pintype "passive"))
      (node (ref "VR5") (pin "3") (pinfunction "Vin_3") (pintype "passive"))
    )
    (net (code "33") (name "5V-BAT") (class "Default")
      (node (ref "Q1") (pin "2") (pinfunction "S_2") (pintype "passive"))
      (node (ref "R1") (pin "1") (pinfunction "1_1") (pintype "passive"))
      (node (ref "SW1") (pin "3") (pinfunction "3_3") (pintype "passive"))
    )
    (net (code "34") (name "5V-EX") (class "Default")
      (node (ref "C12") (pin "2") (pinfunction "2_2") (pintype "passive"))
      (node (ref "C13") (pin "2") (pinfunction "2_2") (pintype "passive"))
      (node (ref "C14") (pin "2") (pinfunction "2_2") (pintype "passive"))
      (node (ref "C15") (pin "2") (pinfunction "2_2") (pintype "passive"))
      (node (ref "C16") (pin "2") (pinfunction "2_2") (pintype "passive"))
      (node (ref "D2") (pin "1") (pinfunction "A_1") (pintype "passive"))
      (node (ref "L2") (pin "2") (pinfunction "2_2") (pintype "passive"))
      (node (ref "Q1") (pin "1") (pinfunction "G_1") (pintype "passive"))
      (node (ref "R8") (pin "2") (pinfunction "2_2") (pintype "passive"))
      (node (ref "R9") (pin "2") (pinfunction "2_2") (pintype "passive"))
    )
    (net (code "35") (name "5V-IN") (class "Default")
      (node (ref "5V") (pin "1") (pinfunction "1_1") (pintype "passive"))
      (node (ref "CN5") (pin "3") (pinfunction "3_3") (pintype "passive"))
      (node (ref "D2") (pin "2") (pinfunction "K_2") (pintype "passive"))
      (node (ref "Q1") (pin "3") (pinfunction "D_3") (pintype "passive"))
      (node (ref "Q2") (pin "2") (pinfunction "S_2") (pintype "passive"))
      (node (ref "Q3") (pin "2") (pinfunction "E_2") (pintype "passive"))
      (node (ref "R1") (pin "2") (pinfunction "2_2") (pintype "passive"))
      (node (ref "R2") (pin "1") (pinfunction "1_1") (pintype "passive"))
      (node (ref "R3") (pin "2") (pinfunction "2_2") (pintype "passive"))
    )
    (net (code "36") (name "24V") (class "Default")
      (node (ref "24V") (pin "1") (pinfunction "1_1") (pintype "passive"))
      (node (ref "C10") (pin "2") (pinfunction "2_2") (pintype "passive"))
      (node (ref "C11") (pin "2") (pinfunction "2_2") (pintype "passive"))
      (node (ref "C9") (pin "2") (pinfunction "2_2") (pintype "passive"))
      (node (ref "D7") (pin "2") (pinfunction "2_2") (pintype "passive"))
      (node (ref "P1") (pin "1") (pinfunction "+_1") (pintype "passive"))
      (node (ref "U2") (pin "8") (pinfunction "VIN_8") (pintype "passive"))
    )
    (net (code "37") (name "GND") (class "Default")
      (node (ref "BAT") (pin "1") (pinfunction "1_1") (pintype "passive"))
      (node (ref "C1") (pin "2") (pinfunction "2_2") (pintype "passive"))
      (node (ref "C10") (pin "1") (pinfunction "1_1") (pintype "passive"))
      (node (ref "C12") (pin "1") (pinfunction "1_1") (pintype "passive"))
      (node (ref "C13") (pin "1") (pinfunction "1_1") (pintype "passive"))
      (node (ref "C14") (pin "1") (pinfunction "1_1") (pintype "passive"))
      (node (ref "C15") (pin "1") (pinfunction "1_1") (pintype "passive"))
      (node (ref "C16") (pin "1") (pinfunction "1_1") (pintype "passive"))
      (node (ref "C17") (pin "1") (pinfunction "1_1") (pintype "passive"))
      (node (ref "C18") (pin "1") (pinfunction "1_1") (pintype "passive"))
      (node (ref "C19") (pin "1") (pinfunction "1_1") (pintype "passive"))
      (node (ref "C2") (pin "2") (pinfunction "2_2") (pintype "passive"))
      (node (ref "C20") (pin "1") (pinfunction "1_1") (pintype "passive"))
      (node (ref "C21") (pin "1") (pinfunction "1_1") (pintype "passive"))
      (node (ref "C22") (pin "1") (pinfunction "1_1") (pintype "passive"))
      (node (ref "C23") (pin "1") (pinfunction "1_1") (pintype "passive"))
      (node (ref "C25") (pin "1") (pinfunction "1_1") (pintype "passive"))
      (node (ref "C26") (pin "1") (pinfunction "1_1") (pintype "passive"))
      (node (ref "C27") (pin "1") (pinfunction "1_1") (pintype "passive"))
      (node (ref "C28") (pin "1") (pinfunction "1_1") (pintype "passive"))
      (node (ref "C29") (pin "1") (pinfunction "1_1") (pintype "passive"))
      (node (ref "C3") (pin "2") (pinfunction "2_2") (pintype "passive"))
      (node (ref "C30") (pin "1") (pinfunction "1_1") (pintype "passive"))
      (node (ref "C31") (pin "1") (pinfunction "1_1") (pintype "passive"))
      (node (ref "C32") (pin "1") (pinfunction "1_1") (pintype "passive"))
      (node (ref "C33") (pin "1") (pinfunction "1_1") (pintype "passive"))
      (node (ref "C34") (pin "1") (pinfunction "1_1") (pintype "passive"))
      (node (ref "C35") (pin "1") (pinfunction "1_1") (pintype "passive"))
      (node (ref "C36") (pin "1") (pinfunction "1_1") (pintype "passive"))
      (node (ref "C37") (pin "1") (pinfunction "1_1") (pintype "passive"))
      (node (ref "C38") (pin "1") (pinfunction "1_1") (pintype "passive"))
      (node (ref "C39") (pin "1") (pinfunction "1_1") (pintype "passive"))
      (node (ref "C4") (pin "2") (pinfunction "2_2") (pintype "passive"))
      (node (ref "C40") (pin "1") (pinfunction "1_1") (pintype "passive"))
      (node (ref "C41") (pin "1") (pinfunction "1_1") (pintype "passive"))
      (node (ref "C42") (pin "1") (pinfunction "1_1") (pintype "passive"))
      (node (ref "C43") (pin "1") (pinfunction "1_1") (pintype "passive"))
      (node (ref "C44") (pin "1") (pinfunction "1_1") (pintype "passive"))
      (node (ref "C45") (pin "1") (pinfunction "1_1") (pintype "passive"))
      (node (ref "C46") (pin "1") (pinfunction "1_1") (pintype "passive"))
      (node (ref "C47") (pin "1") (pinfunction "1_1") (pintype "passive"))
      (node (ref "C48") (pin "1") (pinfunction "1_1") (pintype "passive"))
      (node (ref "C49") (pin "1") (pinfunction "1_1") (pintype "passive"))
      (node (ref "C5") (pin "1") (pinfunction "1_1") (pintype "passive"))
      (node (ref "C50") (pin "1") (pinfunction "1_1") (pintype "passive"))
      (node (ref "C51") (pin "2") (pinfunction "2_2") (pintype "passive"))
      (node (ref "C52") (pin "2") (pinfunction "2_2") (pintype "passive"))
      (node (ref "C53") (pin "2") (pinfunction "2_2") (pintype "passive"))
      (node (ref "C54") (pin "2") (pinfunction "2_2") (pintype "passive"))
      (node (ref "C55") (pin "1") (pinfunction "1_1") (pintype "passive"))
      (node (ref "C56") (pin "2") (pinfunction "2_2") (pintype "passive"))
      (node (ref "C6") (pin "1") (pinfunction "1_1") (pintype "passive"))
      (node (ref "C7") (pin "1") (pinfunction "1_1") (pintype "passive"))
      (node (ref "C8") (pin "1") (pinfunction "1_1") (pintype "passive"))
      (node (ref "C9") (pin "1") (pinfunction "1_1") (pintype "passive"))
      (node (ref "CN5") (pin "1") (pinfunction "1_1") (pintype "passive"))
      (node (ref "D7") (pin "1") (pinfunction "1_1") (pintype "passive"))
      (node (ref "D8") (pin "1") (pinfunction "A_1") (pintype "passive"))
      (node (ref "D9") (pin "1") (pinfunction "1_1") (pintype "passive"))
      (node (ref "D9") (pin "2") (pinfunction "2_2") (pintype "passive"))
      (node (ref "GND") (pin "1") (pinfunction "1_1") (pintype "passive"))
      (node (ref "LED") (pin "3") (pinfunction "3_3") (pintype "passive"))
      (node (ref "LED") (pin "4") (pinfunction "4_4") (pintype "passive"))
      (node (ref "P1") (pin "2") (pinfunction "--_2") (pintype "passive"))
      (node (ref "P2") (pin "2") (pinfunction "2_2") (pintype "passive"))
      (node (ref "P3") (pin "3") (pinfunction "3_3") (pintype "passive"))
      (node (ref "Q5") (pin "2") (pinfunction "E_2") (pintype "passive"))
      (node (ref "Q6") (pin "2") (pinfunction "S_2") (pintype "passive"))
      (node (ref "Q7") (pin "2") (pinfunction "S_2") (pintype "passive"))
      (node (ref "Q8") (pin "2") (pinfunction "S_2") (pintype "passive"))
      (node (ref "R10") (pin "1") (pinfunction "1_1") (pintype "passive"))
      (node (ref "R11") (pin "1") (pinfunction "1_1") (pintype "passive"))
      (node (ref "R13") (pin "2") (pinfunction "2_2") (pintype "passive"))
      (node (ref "R21") (pin "2") (pinfunction "2_2") (pintype "passive"))
      (node (ref "R24") (pin "2") (pinfunction "2_2") (pintype "passive"))
      (node (ref "R30") (pin "1") (pinfunction "1_1") (pintype "passive"))
      (node (ref "R31") (pin "1") (pinfunction "1_1") (pintype "passive"))
      (node (ref "R32") (pin "1") (pinfunction "1_1") (pintype "passive"))
      (node (ref "R9") (pin "1") (pinfunction "1_1") (pintype "passive"))
      (node (ref "S3") (pin "2") (pinfunction "2_2") (pintype "passive"))
      (node (ref "SW2") (pin "3") (pinfunction "3_3") (pintype "passive"))
      (node (ref "SW2") (pin "4") (pinfunction "4_4") (pintype "passive"))
      (node (ref "SW4") (pin "2") (pinfunction "2_2") (pintype "passive"))
      (node (ref "U1") (pin "9") (pinfunction "EP_9") (pintype "passive"))
      (node (ref "U2") (pin "3") (pinfunction "GND_3") (pintype "passive"))
      (node (ref "U2") (pin "5") (pinfunction "CS_5") (pintype "passive"))
      (node (ref "U3") (pin "23") (pinfunction "VSS_1_23") (pintype "power_in"))
      (node (ref "U3") (pin "35") (pinfunction "VSS_2_35") (pintype "power_in"))
      (node (ref "U3") (pin "47") (pinfunction "VSS_3_47") (pintype "power_in"))
      (node (ref "U3") (pin "8") (pinfunction "VSSA_8") (pintype "power_in"))
      (node (ref "U4") (pin "10") (pinfunction "INPB_10") (pintype "passive"))
      (node (ref "U4") (pin "14") (pinfunction "XI_14") (pintype "passive"))
      (node (ref "U4") (pin "15") (pinfunction "RATE_15") (pintype "passive"))
      (node (ref "U4") (pin "5") (pinfunction "AGND_5") (pintype "passive"))
      (node (ref "U4") (pin "9") (pinfunction "INNB_9") (pintype "passive"))
      (node (ref "U5") (pin "2") (pinfunction "GND_2") (pintype "passive"))
      (node (ref "U5") (pin "8") (pinfunction "S_8") (pintype "passive"))
      (node (ref "USB") (pin "5") (pinfunction "GND_5") (pintype "passive"))
      (node (ref "USB2") (pin "4") (pinfunction "GND_4") (pintype "passive"))
      (node (ref "VR1") (pin "1") (pinfunction "GND_1") (pintype "passive"))
      (node (ref "VR2") (pin "1") (pinfunction "GND_1") (pintype "passive"))
      (node (ref "VR3") (pin "1") (pinfunction "GND_1") (pintype "passive"))
      (node (ref "VR4") (pin "1") (pinfunction "GND_1") (pintype "passive"))
      (node (ref "VR5") (pin "1") (pinfunction "GND_1") (pintype "passive"))
    )
    (net (code "38") (name "Net-(C8-Pad2)") (class "Default")
      (node (ref "C8") (pin "2") (pinfunction "2_2") (pintype "passive"))
      (node (ref "R4") (pin "1") (pinfunction "1_1") (pintype "passive"))
    )
    (net (code "39") (name "Net-(D1-A)") (class "Default")
      (node (ref "C1") (pin "1") (pinfunction "1_1") (pintype "passive"))
      (node (ref "C2") (pin "1") (pinfunction "1_1") (pintype "passive"))
      (node (ref "C3") (pin "1") (pinfunction "1_1") (pintype "passive"))
      (node (ref "C4") (pin "1") (pinfunction "1_1") (pintype "passive"))
      (node (ref "D1") (pin "1") (pinfunction "A_1") (pintype "passive"))
      (node (ref "U1") (pin "8") (pinfunction "VOUT_8") (pintype "passive"))
    )
    (net (code "40") (name "Net-(D1-K)") (class "Default")
      (node (ref "D1") (pin "2") (pinfunction "K_2") (pintype "passive"))
      (node (ref "SW1") (pin "2") (pinfunction "2_2") (pintype "passive"))
    )
    (net (code "41") (name "Net-(D8-K)") (class "Default")
      (node (ref "D8") (pin "2") (pinfunction "K_2") (pintype "passive"))
      (node (ref "R3") (pin "1") (pinfunction "1_1") (pintype "passive"))
      (node (ref "R6") (pin "1") (pinfunction "1_1") (pintype "passive"))
    )
    (net (code "42") (name "Net-(P2-Pad3)") (class "Default")
      (node (ref "P2") (pin "3") (pinfunction "3_3") (pintype "passive"))
      (node (ref "R34") (pin "1") (pinfunction "1_1") (pintype "passive"))
    )
    (net (code "43") (name "Net-(P2-Pad4)") (class "Default")
      (node (ref "P2") (pin "4") (pinfunction "4_4") (pintype "passive"))
      (node (ref "R33") (pin "1") (pinfunction "1_1") (pintype "passive"))
    )
    (net (code "44") (name "Net-(P3-Pad1)") (class "Default")
      (node (ref "P3") (pin "1") (pinfunction "1_1") (pintype "passive"))
      (node (ref "R29") (pin "1") (pinfunction "1_1") (pintype "passive"))
    )
    (net (code "45") (name "Net-(Q2-D)") (class "Default")
      (node (ref "F1") (pin "1") (pinfunction "1_1") (pintype "passive"))
      (node (ref "Q2") (pin "3") (pinfunction "D_3") (pintype "passive"))
      (node (ref "R2") (pin "2") (pinfunction "2_2") (pintype "passive"))
    )
    (net (code "46") (name "Net-(Q2-G)") (class "Default")
      (node (ref "Q2") (pin "1") (pinfunction "G_1") (pintype "passive"))
      (node (ref "Q3") (pin "3") (pinfunction "C_3") (pintype "passive"))
      (node (ref "R10") (pin "2") (pinfunction "2_2") (pintype "passive"))
    )
    (net (code "47") (name "Net-(Q3-B)") (class "Default")
      (node (ref "Q3") (pin "1") (pinfunction "B_1") (pintype "passive"))
      (node (ref "R6") (pin "2") (pinfunction "2_2") (pintype "passive"))
    )
    (net (code "48") (name "Net-(Q4-B)") (class "Default")
      (node (ref "Q4") (pin "1") (pinfunction "B_1") (pintype "passive"))
      (node (ref "U4") (pin "2") (pinfunction "BASE_2") (pintype "passive"))
    )
    (net (code "49") (name "Net-(Q5-B)") (class "Default")
      (node (ref "Q5") (pin "1") (pinfunction "B_1") (pintype "passive"))
      (node (ref "R29") (pin "2") (pinfunction "2_2") (pintype "passive"))
    )
    (net (code "50") (name "Net-(Q6-D)") (class "Default")
      (node (ref "Q6") (pin "3") (pinfunction "D_3") (pintype "passive"))
      (node (ref "R26") (pin "1") (pinfunction "1_1") (pintype "passive"))
    )
    (net (code "51") (name "Net-(Q7-D)") (class "Default")
      (node (ref "Q7") (pin "3") (pinfunction "D_3") (pintype "passive"))
      (node (ref "R27") (pin "1") (pinfunction "1_1") (pintype "passive"))
    )
    (net (code "52") (name "Net-(Q8-D)") (class "Default")
      (node (ref "Q8") (pin "3") (pinfunction "D_3") (pintype "passive"))
      (node (ref "R28") (pin "1") (pinfunction "1_1") (pintype "passive"))
    )
    (net (code "53") (name "Net-(R7-Pad1)") (class "Default")
      (node (ref "R7") (pin "1") (pinfunction "1_1") (pintype "passive"))
      (node (ref "SW2") (pin "1") (pinfunction "1_1") (pintype "passive"))
      (node (ref "SW2") (pin "2") (pinfunction "2_2") (pintype "passive"))
    )
    (net (code "54") (name "Net-(U1-BAT)") (class "Default")
      (node (ref "C7") (pin "2") (pinfunction "2_2") (pintype "passive"))
      (node (ref "R5") (pin "1") (pinfunction "1_1") (pintype "passive"))
      (node (ref "U1") (pin "6") (pinfunction "BAT_6") (pintype "passive"))
    )
    (net (code "55") (name "Net-(U1-KEY)") (class "Default")
      (node (ref "R7") (pin "2") (pinfunction "2_2") (pintype "passive"))
      (node (ref "U1") (pin "5") (pinfunction "KEY_5") (pintype "passive"))
    )
    (net (code "56") (name "Net-(U1-LED1)") (class "Default")
      (node (ref "D3") (pin "A") (pinfunction "A_A") (pintype "passive"))
      (node (ref "D4") (pin "K") (pinfunction "K_K") (pintype "passive"))
      (node (ref "U1") (pin "2") (pinfunction "LED1_2") (pintype "passive"))
    )
    (net (code "57") (name "Net-(U1-LED2)") (class "Default")
      (node (ref "D5") (pin "A") (pinfunction "A_A") (pintype "passive"))
      (node (ref "D6") (pin "K") (pinfunction "K_K") (pintype "passive"))
      (node (ref "U1") (pin "3") (pinfunction "LED2_3") (pintype "passive"))
    )
    (net (code "58") (name "Net-(U1-LED3)") (class "Default")
      (node (ref "D3") (pin "K") (pinfunction "K_K") (pintype "passive"))
      (node (ref "D4") (pin "A") (pinfunction "A_A") (pintype "passive"))
      (node (ref "D5") (pin "K") (pinfunction "K_K") (pintype "passive"))
      (node (ref "D6") (pin "A") (pinfunction "A_A") (pintype "passive"))
      (node (ref "U1") (pin "4") (pinfunction "LED3_4") (pintype "passive"))
    )
    (net (code "59") (name "Net-(U1-SW)") (class "Default")
      (node (ref "L1") (pin "1") (pinfunction "1_1") (pintype "passive"))
      (node (ref "U1") (pin "7") (pinfunction "SW_7") (pintype "passive"))
    )
    (net (code "60") (name "Net-(U1-VIN)") (class "Default")
      (node (ref "C5") (pin "2") (pinfunction "2_2") (pintype "passive"))
      (node (ref "R4") (pin "2") (pinfunction "2_2") (pintype "passive"))
      (node (ref "U1") (pin "1") (pinfunction "VIN_1") (pintype "passive"))
      (node (ref "USB") (pin "1") (pinfunction "VCC_1") (pintype "passive"))
    )
    (net (code "61") (name "Net-(U2-EP)") (class "Default")
      (node (ref "D9") (pin "3") (pinfunction "3_3") (pintype "passive"))
      (node (ref "L2") (pin "1") (pinfunction "1_1") (pintype "passive"))
      (node (ref "U2") (pin "2") (pinfunction "SW_2") (pintype "passive"))
      (node (ref "U2") (pin "9") (pinfunction "EP_9") (pintype "passive"))
    )
    (net (code "62") (name "Net-(U2-FB)") (class "Default")
      (node (ref "R11") (pin "2") (pinfunction "2_2") (pintype "passive"))
      (node (ref "R8") (pin "1") (pinfunction "1_1") (pintype "passive"))
      (node (ref "U2") (pin "4") (pinfunction "FB_4") (pintype "passive"))
    )
    (net (code "63") (name "Net-(U2-VC)") (class "Default")
      (node (ref "C11") (pin "1") (pinfunction "1_1") (pintype "passive"))
      (node (ref "U2") (pin "7") (pinfunction "VC_7") (pintype "passive"))
    )
    (net (code "64") (name "Net-(U3B-VDDA)") (class "Default")
      (node (ref "C45") (pin "2") (pinfunction "2_2") (pintype "passive"))
      (node (ref "C46") (pin "2") (pinfunction "2_2") (pintype "passive"))
      (node (ref "L3") (pin "2") (pinfunction "2_2") (pintype "passive"))
      (node (ref "U3") (pin "9") (pinfunction "VDDA_9") (pintype "power_in"))
    )
    (net (code "65") (name "Net-(U4-INNA)") (class "Default")
      (node (ref "C24") (pin "1") (pinfunction "1_1") (pintype "passive"))
      (node (ref "R16") (pin "1") (pinfunction "1_1") (pintype "passive"))
      (node (ref "U4") (pin "7") (pinfunction "INNA_7") (pintype "passive"))
    )
    (net (code "66") (name "Net-(U4-INPA)") (class "Default")
      (node (ref "C24") (pin "2") (pinfunction "2_2") (pintype "passive"))
      (node (ref "R14") (pin "1") (pinfunction "1_1") (pintype "passive"))
      (node (ref "U4") (pin "8") (pinfunction "INPA_8") (pintype "passive"))
    )
    (net (code "67") (name "Net-(U4-VBG)") (class "Default")
      (node (ref "C23") (pin "2") (pinfunction "2_2") (pintype "passive"))
      (node (ref "U4") (pin "6") (pinfunction "VBG_6") (pintype "passive"))
    )
    (net (code "68") (name "Net-(U4-VFB)") (class "Default")
      (node (ref "R12") (pin "1") (pinfunction "1_1") (pintype "passive"))
      (node (ref "R13") (pin "1") (pinfunction "1_1") (pintype "passive"))
      (node (ref "U4") (pin "4") (pinfunction "VFB_4") (pintype "passive"))
    )
    (net (code "69") (name "Net-(U5-CANH)") (class "Default")
      (node (ref "L4") (pin "1") (pinfunction "1_1") (pintype "passive"))
      (node (ref "R23") (pin "2") (pinfunction "2_2") (pintype "passive"))
      (node (ref "U5") (pin "7") (pinfunction "CANH_7") (pintype "passive"))
    )
    (net (code "70") (name "Net-(U5-CANL)") (class "Default")
      (node (ref "L4") (pin "2") (pinfunction "2_2") (pintype "passive"))
      (node (ref "R23") (pin "1") (pinfunction "1_1") (pintype "passive"))
      (node (ref "U5") (pin "6") (pinfunction "CANL_6") (pintype "passive"))
    )
    (net (code "71") (name "Net-(VR2-Vout)") (class "Default")
      (node (ref "C25") (pin "2") (pinfunction "2_2") (pintype "passive"))
      (node (ref "C28") (pin "2") (pinfunction "2_2") (pintype "passive"))
      (node (ref "R15") (pin "1") (pinfunction "1_1") (pintype "passive"))
      (node (ref "VR2") (pin "2") (pinfunction "Vout_2") (pintype "passive"))
    )
    (net (code "72") (name "Net-(VR3-Vout)") (class "Default")
      (node (ref "C31") (pin "2") (pinfunction "2_2") (pintype "passive"))
      (node (ref "C32") (pin "2") (pinfunction "2_2") (pintype "passive"))
      (node (ref "R17") (pin "1") (pinfunction "1_1") (pintype "passive"))
      (node (ref "VR3") (pin "2") (pinfunction "Vout_2") (pintype "passive"))
    )
    (net (code "73") (name "Net-(VR4-Vout)") (class "Default")
      (node (ref "C43") (pin "2") (pinfunction "2_2") (pintype "passive"))
      (node (ref "C44") (pin "2") (pinfunction "2_2") (pintype "passive"))
      (node (ref "R18") (pin "1") (pinfunction "1_1") (pintype "passive"))
      (node (ref "VR4") (pin "2") (pinfunction "Vout_2") (pintype "passive"))
    )
    (net (code "74") (name "Net-(VR5-Vout)") (class "Default")
      (node (ref "C49") (pin "2") (pinfunction "2_2") (pintype "passive"))
      (node (ref "C50") (pin "2") (pinfunction "2_2") (pintype "passive"))
      (node (ref "R19") (pin "1") (pinfunction "1_1") (pintype "passive"))
      (node (ref "VR5") (pin "2") (pinfunction "Vout_2") (pintype "passive"))
    )
    (net (code "75") (name "S1-R(E+)") (class "Default")
      (node (ref "C22") (pin "2") (pinfunction "2_2") (pintype "passive"))
      (node (ref "Q4") (pin "3") (pinfunction "C_3") (pintype "passive"))
      (node (ref "R12") (pin "2") (pinfunction "2_2") (pintype "passive"))
      (node (ref "S1") (pin "2") (pinfunction "2_2") (pintype "passive"))
      (node (ref "U4") (pin "3") (pinfunction "AVDD_3") (pintype "passive"))
    )
    (net (code "76") (name "VBAT(3.7V)") (class "Default")
      (node (ref "3.7-4.2V") (pin "1") (pinfunction "1_1") (pintype "passive"))
      (node (ref "BAT") (pin "2") (pinfunction "2_2") (pintype "passive"))
      (node (ref "C6") (pin "2") (pinfunction "2_2") (pintype "passive"))
      (node (ref "L1") (pin "2") (pinfunction "2_2") (pintype "passive"))
      (node (ref "R5") (pin "2") (pinfunction "2_2") (pintype "passive"))
    )
    (net (code "77") (name "unconnected-(BAT-Pad3)") (class "Default")
      (node (ref "BAT") (pin "3") (pinfunction "3_3") (pintype "passive+no_connect"))
    )
    (net (code "78") (name "unconnected-(BAT-Pad4)") (class "Default")
      (node (ref "BAT") (pin "4") (pinfunction "4_4") (pintype "passive+no_connect"))
    )
    (net (code "79") (name "unconnected-(CAN-Pad3)") (class "Default")
      (node (ref "CAN") (pin "3") (pinfunction "3_3") (pintype "passive+no_connect"))
    )
    (net (code "80") (name "unconnected-(CAN-Pad4)") (class "Default")
      (node (ref "CAN") (pin "4") (pinfunction "4_4") (pintype "passive+no_connect"))
    )
    (net (code "81") (name "unconnected-(CN5-Pad4)") (class "Default")
      (node (ref "CN5") (pin "4") (pinfunction "4_4") (pintype "passive+no_connect"))
    )
    (net (code "82") (name "unconnected-(CN5-Pad5)") (class "Default")
      (node (ref "CN5") (pin "5") (pinfunction "5_5") (pintype "passive+no_connect"))
    )
    (net (code "83") (name "unconnected-(LEDL-Pad5)") (class "Default")
      (node (ref "LEDL") (pin "5") (pinfunction "5_5") (pintype "passive+no_connect"))
    )
    (net (code "84") (name "unconnected-(LEDL-Pad6)") (class "Default")
      (node (ref "LEDL") (pin "6") (pinfunction "6_6") (pintype "passive+no_connect"))
    )
    (net (code "85") (name "unconnected-(LEDR-Pad5)") (class "Default")
      (node (ref "LEDR") (pin "5") (pinfunction "5_5") (pintype "passive+no_connect"))
    )
    (net (code "86") (name "unconnected-(LEDR-Pad6)") (class "Default")
      (node (ref "LEDR") (pin "6") (pinfunction "6_6") (pintype "passive+no_connect"))
    )
    (net (code "87") (name "unconnected-(S1-Pad4)") (class "Default")
      (node (ref "S1") (pin "4") (pinfunction "4_4") (pintype "passive+no_connect"))
    )
    (net (code "88") (name "unconnected-(S1-Pad5)") (class "Default")
      (node (ref "S1") (pin "5") (pinfunction "5_5") (pintype "passive+no_connect"))
    )
    (net (code "89") (name "unconnected-(S2-Pad4)") (class "Default")
      (node (ref "S2") (pin "4") (pinfunction "4_4") (pintype "passive+no_connect"))
    )
    (net (code "90") (name "unconnected-(S2-Pad5)") (class "Default")
      (node (ref "S2") (pin "5") (pinfunction "5_5") (pintype "passive+no_connect"))
    )
    (net (code "91") (name "unconnected-(S3-Pad4)") (class "Default")
      (node (ref "S3") (pin "4") (pinfunction "4_4") (pintype "passive+no_connect"))
    )
    (net (code "92") (name "unconnected-(S3-Pad5)") (class "Default")
      (node (ref "S3") (pin "5") (pinfunction "5_5") (pintype "passive+no_connect"))
    )
    (net (code "93") (name "unconnected-(S4-Pad4)") (class "Default")
      (node (ref "S4") (pin "4") (pinfunction "4_4") (pintype "passive+no_connect"))
    )
    (net (code "94") (name "unconnected-(S4-Pad5)") (class "Default")
      (node (ref "S4") (pin "5") (pinfunction "5_5") (pintype "passive+no_connect"))
    )
    (net (code "95") (name "unconnected-(SW1-Pad1)") (class "Default")
      (node (ref "SW1") (pin "1") (pinfunction "1_1") (pintype "passive+no_connect"))
    )
    (net (code "96") (name "unconnected-(U2-NC-Pad1)") (class "Default")
      (node (ref "U2") (pin "1") (pinfunction "NC_1") (pintype "passive"))
    )
    (net (code "97") (name "unconnected-(U2-NC-Pad6)") (class "Default")
      (node (ref "U2") (pin "6") (pinfunction "NC_6") (pintype "passive"))
    )
    (net (code "98") (name "unconnected-(U3A-PA0-WKUP-Pad10)") (class "Default")
      (node (ref "U3") (pin "10") (pinfunction "PA0-WKUP_10") (pintype "bidirectional+no_connect"))
    )
    (net (code "99") (name "unconnected-(U3A-PA1-Pad11)") (class "Default")
      (node (ref "U3") (pin "11") (pinfunction "PA1_11") (pintype "bidirectional+no_connect"))
    )
    (net (code "100") (name "unconnected-(U3A-PA2-Pad12)") (class "Default")
      (node (ref "U3") (pin "12") (pinfunction "PA2_12") (pintype "bidirectional+no_connect"))
    )
    (net (code "101") (name "unconnected-(U3A-PA3-Pad13)") (class "Default")
      (node (ref "U3") (pin "13") (pinfunction "PA3_13") (pintype "bidirectional+no_connect"))
    )
    (net (code "102") (name "unconnected-(U3A-PA4-Pad14)") (class "Default")
      (node (ref "U3") (pin "14") (pinfunction "PA4_14") (pintype "bidirectional+no_connect"))
    )
    (net (code "103") (name "unconnected-(U3A-PA8-Pad29)") (class "Default")
      (node (ref "U3") (pin "29") (pinfunction "PA8_29") (pintype "bidirectional+no_connect"))
    )
    (net (code "104") (name "unconnected-(U3A-PA9-Pad30)") (class "Default")
      (node (ref "U3") (pin "30") (pinfunction "PA9_30") (pintype "bidirectional+no_connect"))
    )
    (net (code "105") (name "unconnected-(U3A-PA10-Pad31)") (class "Default")
      (node (ref "U3") (pin "31") (pinfunction "PA10_31") (pintype "bidirectional+no_connect"))
    )
    (net (code "106") (name "unconnected-(U3A-PA15-Pad38)") (class "Default")
      (node (ref "U3") (pin "38") (pinfunction "PA15_38") (pintype "bidirectional+no_connect"))
    )
    (net (code "107") (name "unconnected-(U3A-PB3-Pad39)") (class "Default")
      (node (ref "U3") (pin "39") (pinfunction "PB3_39") (pintype "bidirectional+no_connect"))
    )
    (net (code "108") (name "unconnected-(U3A-PB4-Pad40)") (class "Default")
      (node (ref "U3") (pin "40") (pinfunction "PB4_40") (pintype "bidirectional+no_connect"))
    )
    (net (code "109") (name "unconnected-(U3A-PB5-Pad41)") (class "Default")
      (node (ref "U3") (pin "41") (pinfunction "PB5_41") (pintype "bidirectional+no_connect"))
    )
    (net (code "110") (name "unconnected-(U3A-PB6-Pad42)") (class "Default")
      (node (ref "U3") (pin "42") (pinfunction "PB6_42") (pintype "bidirectional"))
    )
    (net (code "111") (name "unconnected-(U3A-PB10-Pad21)") (class "Default")
      (node (ref "U3") (pin "21") (pinfunction "PB10_21") (pintype "bidirectional+no_connect"))
    )
    (net (code "112") (name "unconnected-(U3A-PB11-Pad22)") (class "Default")
      (node (ref "U3") (pin "22") (pinfunction "PB11_22") (pintype "bidirectional+no_connect"))
    )
    (net (code "113") (name "unconnected-(U3A-PB12-Pad25)") (class "Default")
      (node (ref "U3") (pin "25") (pinfunction "PB12_25") (pintype "bidirectional+no_connect"))
    )
    (net (code "114") (name "unconnected-(U3A-PB13-Pad26)") (class "Default")
      (node (ref "U3") (pin "26") (pinfunction "PB13_26") (pintype "bidirectional+no_connect"))
    )
    (net (code "115") (name "unconnected-(U3A-PB14-Pad27)") (class "Default")
      (node (ref "U3") (pin "27") (pinfunction "PB14_27") (pintype "bidirectional+no_connect"))
    )
    (net (code "116") (name "unconnected-(U3A-PB15-Pad28)") (class "Default")
      (node (ref "U3") (pin "28") (pinfunction "PB15_28") (pintype "bidirectional+no_connect"))
    )
    (net (code "117") (name "unconnected-(U3A-PC13-TAMPER-RTC-Pad2)") (class "Default")
      (node (ref "U3") (pin "2") (pinfunction "PC13-TAMPER-RTC_2") (pintype "bidirectional+no_connect"))
    )
    (net (code "118") (name "unconnected-(U3A-PC14-OSC32_IN-Pad3)") (class "Default")
      (node (ref "U3") (pin "3") (pinfunction "PC14-OSC32_IN_3") (pintype "bidirectional+no_connect"))
    )
    (net (code "119") (name "unconnected-(U3A-PC15-OSC32_OUT-Pad4)") (class "Default")
      (node (ref "U3") (pin "4") (pinfunction "PC15-OSC32_OUT_4") (pintype "bidirectional+no_connect"))
    )
    (net (code "120") (name "unconnected-(U4-XO-Pad13)") (class "Default")
      (node (ref "U4") (pin "13") (pinfunction "XO_13") (pintype "passive+no_connect"))
    )
    (net (code "121") (name "unconnected-(USB-D+-Pad3)") (class "Default")
      (node (ref "USB") (pin "3") (pinfunction "D+_3") (pintype "passive+no_connect"))
    )
    (net (code "122") (name "unconnected-(USB-D--Pad2)") (class "Default")
      (node (ref "USB") (pin "2") (pinfunction "D-_2") (pintype "passive+no_connect"))
    )
    (net (code "123") (name "unconnected-(USB-ID-Pad4)") (class "Default")
      (node (ref "USB") (pin "4") (pinfunction "ID_4") (pintype "passive+no_connect"))
    )
    (net (code "124") (name "unconnected-(USB-SHELL-Pad6)") (class "Default")
      (node (ref "USB") (pin "6") (pinfunction "SHELL_6") (pintype "passive+no_connect"))
    )
    (net (code "125") (name "unconnected-(USB2-D+-Pad3)") (class "Default")
      (node (ref "USB2") (pin "3") (pinfunction "D+_3") (pintype "passive+no_connect"))
    )
    (net (code "126") (name "unconnected-(USB2-D--Pad2)") (class "Default")
      (node (ref "USB2") (pin "2") (pinfunction "D-_2") (pintype "passive+no_connect"))
    )
    (net (code "127") (name "unconnected-(USB2-SHLD-Pad0)") (class "Default")
      (node (ref "USB2") (pin "0") (pinfunction "SHLD_0") (pintype "passive+no_connect"))
    )
    (net (code "128") (name "unconnected-(USB2-SHLD-Pad0)_1") (class "Default")
      (node (ref "USB2") (pin "0") (pinfunction "SHLD_0") (pintype "passive+no_connect"))
    )
  )
)
